# 0to5V.net
KiCad netlist of a schematic drawn in Altium Designer
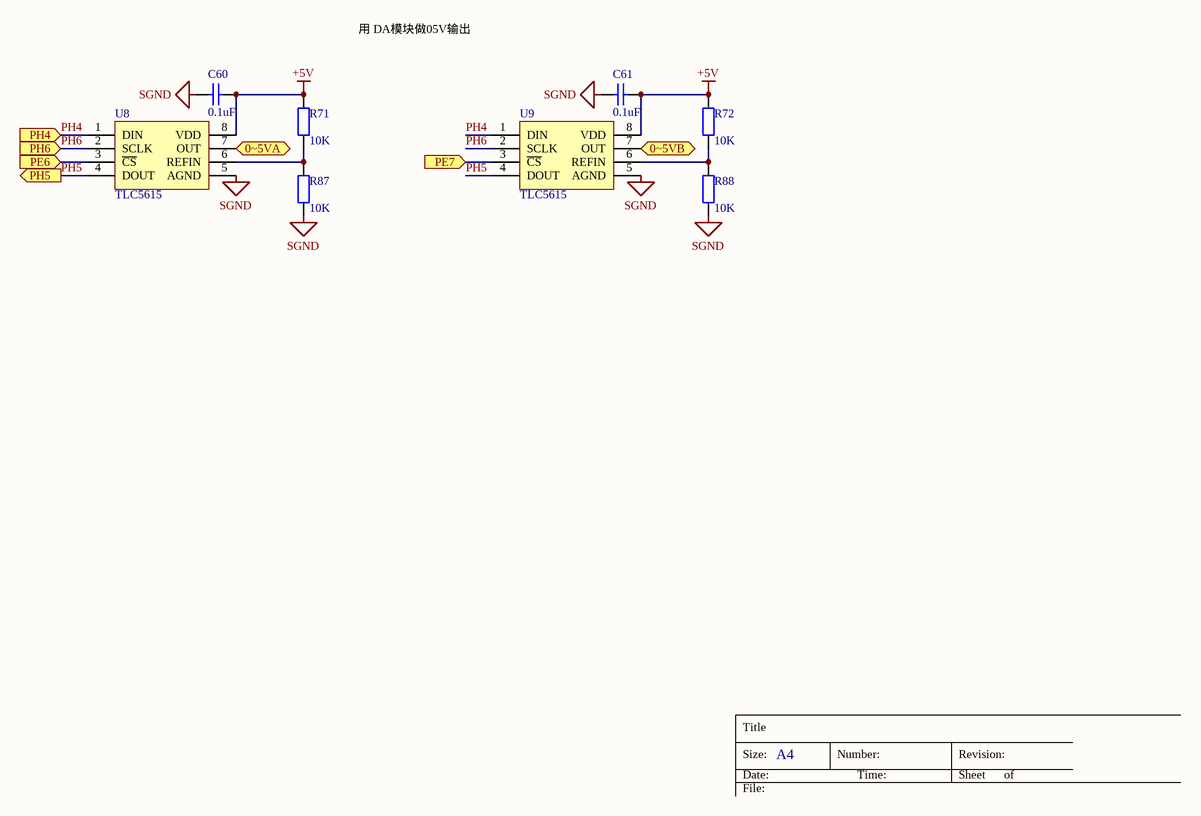
[diagram p0: 0to5V输出模块.SchDoc]

(export (version "E")
  (design (tool "Eeschema 10.0.6"))
  (components
    (comp (ref "C60")
      (value "0.1uF")
      (footprint "0603-L")
      (description "Capacitor")
      (fields (field (name "Comment") "Cap") (field (name "PUBLISHER") "Altium Limited"))
      (libsource (lib "Miscellaneous Devices") (part "Cap"))
    )
    (comp (ref "C61")
      (value "0.1uF")
      (footprint "0603-L")
      (description "Capacitor")
      (fields (field (name "Comment") "Cap") (field (name "PUBLISHER") "Altium Limited"))
      (libsource (lib "Miscellaneous Devices") (part "Cap"))
    )
    (comp (ref "R71")
      (value "10K")
      (footprint "0603-L")
      (description "Resistor")
      (fields (field (name "Comment") "Res2") (field (name "PUBLISHER") "Altium Limited"))
      (libsource (lib "Miscellaneous Devices") (part "Res2"))
    )
    (comp (ref "R72")
      (value "10K")
      (footprint "0603-L")
      (description "Resistor")
      (fields (field (name "Comment") "Res2") (field (name "PUBLISHER") "Altium Limited"))
      (libsource (lib "Miscellaneous Devices") (part "Res2"))
    )
    (comp (ref "R87")
      (value "10K")
      (footprint "0603-L")
      (description "Resistor")
      (fields (field (name "Comment") "Res2") (field (name "PUBLISHER") "Altium Limited"))
      (libsource (lib "Miscellaneous Devices") (part "Res2"))
    )
    (comp (ref "R88")
      (value "10K")
      (footprint "0603-L")
      (description "Resistor")
      (fields (field (name "Comment") "Res2") (field (name "PUBLISHER") "Altium Limited"))
      (libsource (lib "Miscellaneous Devices") (part "Res2"))
    )
    (comp (ref "U8") (value "TLC5615") (footprint "TLC5615") (libsource (lib "整车控制器") (part "TLC5615")))
    (comp (ref "U9") (value "TLC5615") (footprint "TLC5615") (libsource (lib "整车控制器") (part "TLC5615")))
  )
  (nets
    (net (code "1") (name "+5V") (class "Default")
      (node (ref "C60") (pin "1") (pinfunction "1_1") (pintype "passive"))
      (node (ref "C61") (pin "1") (pinfunction "1_1") (pintype "passive"))
      (node (ref "R71") (pin "2") (pinfunction "2_2") (pintype "passive"))
      (node (ref "R72") (pin "2") (pinfunction "2_2") (pintype "passive"))
      (node (ref "U8") (pin "8") (pinfunction "VDD_8") (pintype "passive"))
      (node (ref "U9") (pin "8") (pinfunction "VDD_8") (pintype "passive"))
    )
    (net (code "2") (name "/0~5VA") (class "Default")
      (node (ref "U8") (pin "7") (pinfunction "OUT_7") (pintype "passive"))
    )
    (net (code "3") (name "/0~5VB") (class "Default")
      (node (ref "U9") (pin "7") (pinfunction "OUT_7") (pintype "passive"))
    )
    (net (code "4") (name "/PE6") (class "Default")
      (node (ref "U8") (pin "3") (pinfunction "~{CS}_3") (pintype "passive"))
    )
    (net (code "5") (name "/PE7") (class "Default")
      (node (ref "U9") (pin "3") (pinfunction "~{CS}_3") (pintype "passive"))
    )
    (net (code "6") (name "/PH4") (class "Default")
      (node (ref "U8") (pin "1") (pinfunction "DIN_1") (pintype "passive"))
      (node (ref "U9") (pin "1") (pinfunction "DIN_1") (pintype "passive"))
    )
    (net (code "7") (name "/PH5") (class "Default")
      (node (ref "U8") (pin "4") (pinfunction "DOUT_4") (pintype "passive"))
      (node (ref "U9") (pin "4") (pinfunction "DOUT_4") (pintype "passive"))
    )
    (net (code "8") (name "/PH6") (class "Default")
      (node (ref "U8") (pin "2") (pinfunction "SCLK_2") (pintype "passive"))
      (node (ref "U9") (pin "2") (pinfunction "SCLK_2") (pintype "passive"))
    )
    (net (code "9") (name "Net-(U8-REFIN)") (class "Default")
      (node (ref "R71") (pin "1") (pinfunction "1_1") (pintype "passive"))
      (node (ref "R87") (pin "2") (pinfunction "2_2") (pintype "passive"))
      (node (ref "U8") (pin "6") (pinfunction "REFIN_6") (pintype "passive"))
    )
    (net (code "10") (name "Net-(U9-REFIN)") (class "Default")
      (node (ref "R72") (pin "1") (pinfunction "1_1") (pintype "passive"))
      (node (ref "R88") (pin "2") (pinfunction "2_2") (pintype "passive"))
      (node (ref "U9") (pin "6") (pinfunction "REFIN_6") (pintype "passive"))
    )
    (net (code "11") (name "SGND") (class "Default")
      (node (ref "C60") (pin "2") (pinfunction "2_2") (pintype "passive"))
      (node (ref "C61") (pin "2") (pinfunction "2_2") (pintype "passive"))
      (node (ref "R87") (pin "1") (pinfunction "1_1") (pintype "passive"))
      (node (ref "R88") (pin "1") (pinfunction "1_1") (pintype "passive"))
      (node (ref "U8") (pin "5") (pinfunction "AGND_5") (pintype "passive"))
      (node (ref "U9") (pin "5") (pinfunction "AGND_5") (pintype "passive"))
    )
  )
)
